# MainBoard_v1_1.net
KiCad netlist of a schematic drawn in EAGLE
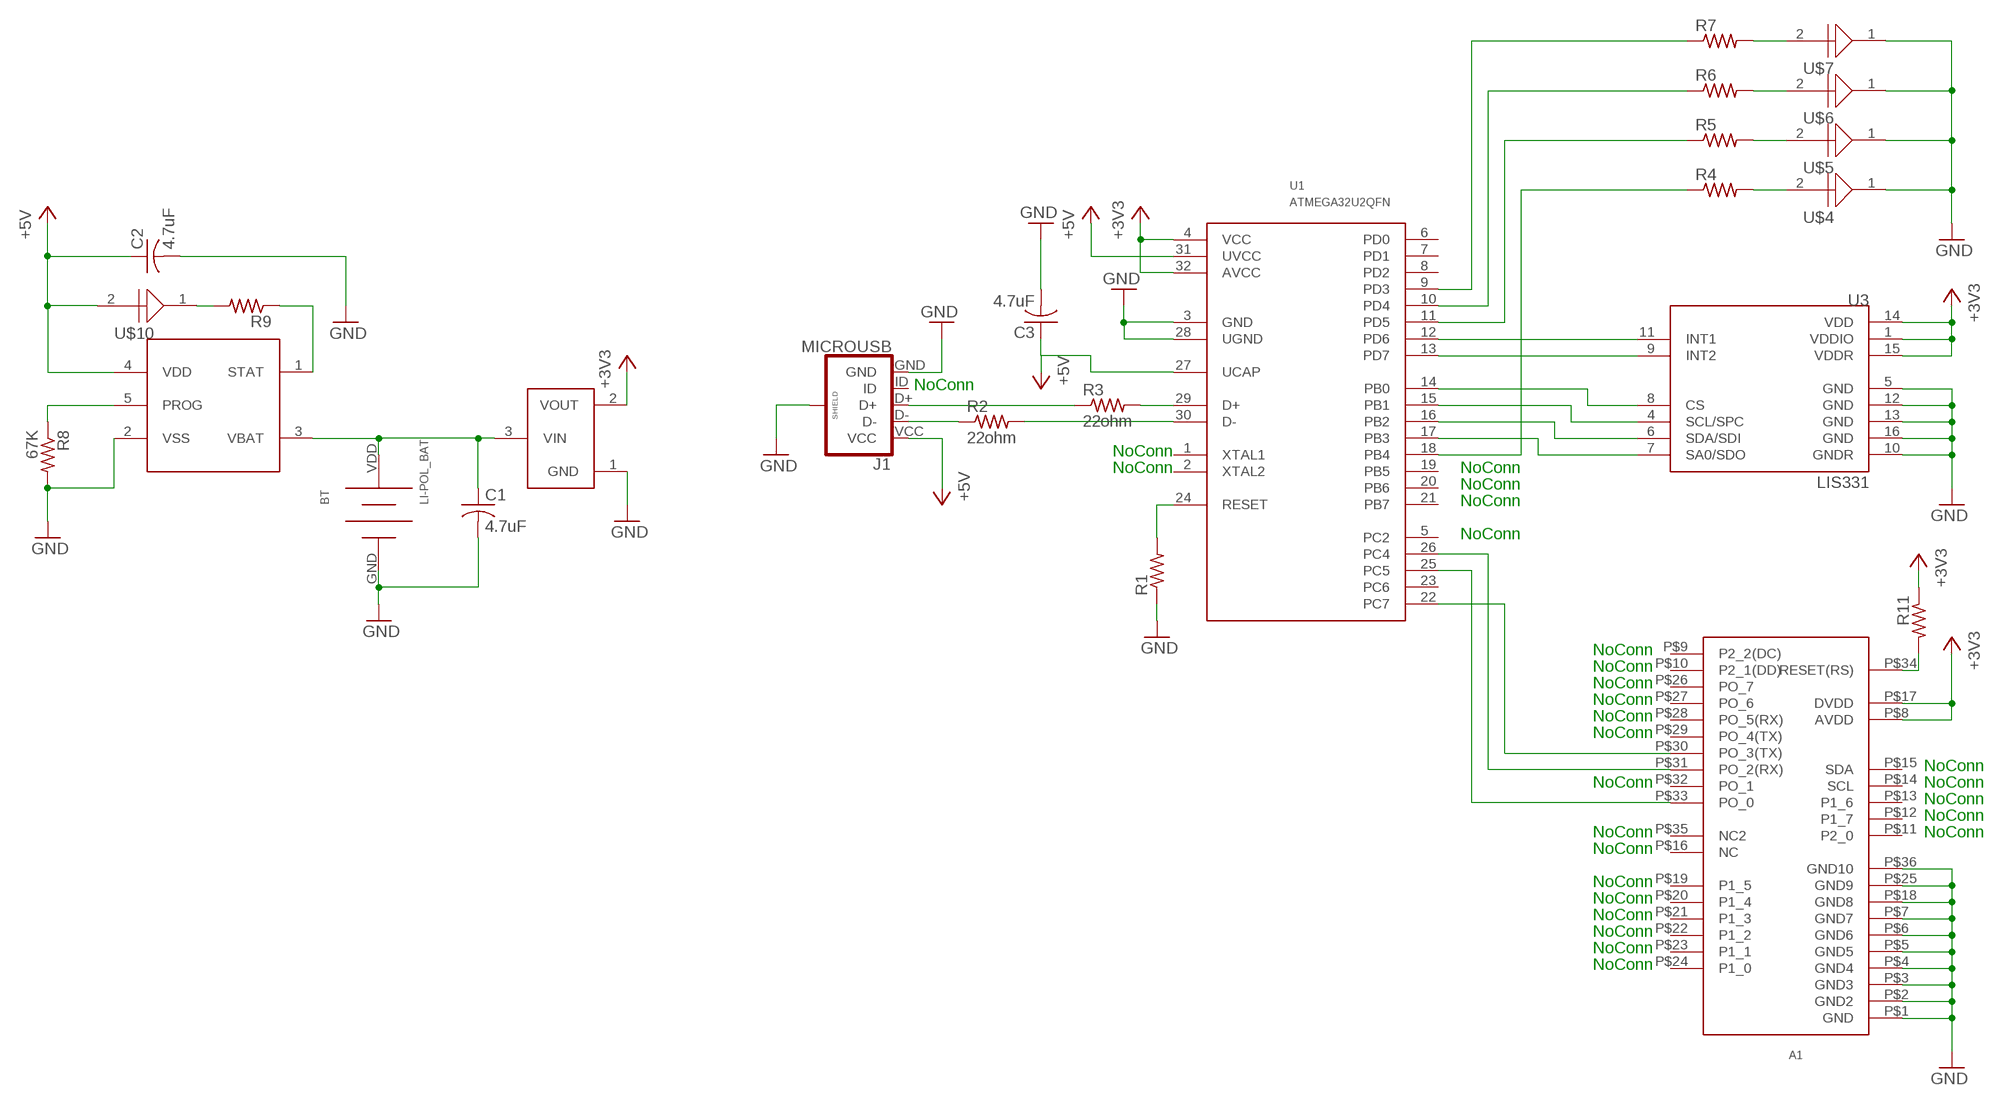
[diagram p0: schematic, sheet 1]

(export (version "E")
  (design (tool "Eeschema 10.0.6"))
  (components
    (comp (ref "A1")
      (value "BLE113-A")
      (footprint "eagle-import:BLUETOOTHNS")
      (libsource (lib "eagle-import") (part "BLE113-A"))
    )
    (comp (ref "BT")
      (value "LI-POL_BAT")
      (footprint "eagle-import:LI-POLY_28")
      (libsource (lib "eagle-import") (part "LI-POL_BAT"))
    )
    (comp (ref "C1")
      (value "4.7uF")
      (footprint "eagle-import:C0402")
      (libsource (lib "eagle-import") (part "C-USC0402"))
    )
    (comp (ref "C2")
      (value "4.7uF")
      (footprint "eagle-import:C0402")
      (libsource (lib "eagle-import") (part "C-USC0402"))
    )
    (comp (ref "C3")
      (value "4.7uF")
      (footprint "eagle-import:C0402")
      (libsource (lib "eagle-import") (part "C-USC0402"))
    )
    (comp (ref "J1")
      (value "MICROUSB")
      (footprint "eagle-import:MICROUSB")
      (libsource (lib "eagle-import") (part "MICROUSB"))
    )
    (comp (ref "R1")
      (value "R-US_R0402")
      (footprint "eagle-import:R0402")
      (libsource (lib "eagle-import") (part "R-US_R0402"))
    )
    (comp (ref "R2")
      (value "22ohm")
      (footprint "eagle-import:R0402")
      (libsource (lib "eagle-import") (part "R-US_R0402"))
    )
    (comp (ref "R3")
      (value "22ohm")
      (footprint "eagle-import:R0402")
      (libsource (lib "eagle-import") (part "R-US_R0402"))
    )
    (comp (ref "R4")
      (value "R-US_R0402")
      (footprint "eagle-import:R0402")
      (libsource (lib "eagle-import") (part "R-US_R0402"))
    )
    (comp (ref "R5")
      (value "R-US_R0402")
      (footprint "eagle-import:R0402")
      (libsource (lib "eagle-import") (part "R-US_R0402"))
    )
    (comp (ref "R6")
      (value "R-US_R0402")
      (footprint "eagle-import:R0402")
      (libsource (lib "eagle-import") (part "R-US_R0402"))
    )
    (comp (ref "R7")
      (value "R-US_R0402")
      (footprint "eagle-import:R0402")
      (libsource (lib "eagle-import") (part "R-US_R0402"))
    )
    (comp (ref "R8")
      (value "67K")
      (footprint "eagle-import:R0402")
      (libsource (lib "eagle-import") (part "R-US_R0402"))
    )
    (comp (ref "R9")
      (value "R-US_R0402")
      (footprint "eagle-import:R0402")
      (libsource (lib "eagle-import") (part "R-US_R0402"))
    )
    (comp (ref "R11")
      (value "R-US_R0402")
      (footprint "eagle-import:R0402")
      (libsource (lib "eagle-import") (part "R-US_R0402"))
    )
    (comp (ref "U$4")
      (value "LED_0402")
      (footprint "eagle-import:R0402")
      (libsource (lib "eagle-import") (part "LED_0402"))
    )
    (comp (ref "U$5")
      (value "LED_0402")
      (footprint "eagle-import:R0402")
      (libsource (lib "eagle-import") (part "LED_0402"))
    )
    (comp (ref "U$6")
      (value "LED_0402")
      (footprint "eagle-import:R0402")
      (libsource (lib "eagle-import") (part "LED_0402"))
    )
    (comp (ref "U$7")
      (value "LED_0402")
      (footprint "eagle-import:R0402")
      (libsource (lib "eagle-import") (part "LED_0402"))
    )
    (comp (ref "U$10")
      (value "LED_0402")
      (footprint "eagle-import:R0402")
      (libsource (lib "eagle-import") (part "LED_0402"))
    )
    (comp (ref "U1")
      (value "ATMEGA32U2QFN")
      (footprint "eagle-import:QFN-32")
      (libsource (lib "eagle-import") (part "ATMEGA32U2QFN"))
    )
    (comp (ref "U2")
      (value "MCP738312")
      (footprint "eagle-import:SOT23-5")
      (libsource (lib "eagle-import") (part "MCP738312"))
    )
    (comp (ref "U3")
      (value "LIS331")
      (footprint "eagle-import:LGA16-3MM")
      (libsource (lib "eagle-import") (part "LIS331"))
    )
    (comp (ref "U5")
      (value "REGULATOR")
      (footprint "eagle-import:SOT23-3")
      (libsource (lib "eagle-import") (part "REGULATOR"))
    )
  )
  (nets
    (net (code "1") (name "+3V3") (class "Default")
      (node (ref "A1") (pin "P$17") (pinfunction "DVDD_P$17") (pintype "bidirectional"))
      (node (ref "A1") (pin "P$8") (pinfunction "AVDD_P$8") (pintype "bidirectional"))
      (node (ref "R11") (pin "1") (pinfunction "1_1") (pintype "passive"))
      (node (ref "U1") (pin "32") (pinfunction "AVCC_32") (pintype "bidirectional"))
      (node (ref "U1") (pin "4") (pinfunction "VCC_4") (pintype "bidirectional"))
      (node (ref "U3") (pin "1") (pinfunction "VDDIO_1") (pintype "bidirectional"))
      (node (ref "U3") (pin "14") (pinfunction "VDD_14") (pintype "bidirectional"))
      (node (ref "U3") (pin "15") (pinfunction "VDDR_15") (pintype "bidirectional"))
      (node (ref "U5") (pin "2") (pinfunction "VOUT_2") (pintype "bidirectional"))
    )
    (net (code "2") (name "+5V") (class "Default")
      (node (ref "C2") (pin "1") (pinfunction "1_1") (pintype "passive"))
      (node (ref "C3") (pin "1") (pinfunction "1_1") (pintype "passive"))
      (node (ref "J1") (pin "VCC") (pinfunction "VCC_VCC") (pintype "bidirectional"))
      (node (ref "U$10") (pin "2") (pinfunction "P2_2") (pintype "bidirectional"))
      (node (ref "U1") (pin "27") (pinfunction "UCAP_27") (pintype "bidirectional"))
      (node (ref "U1") (pin "31") (pinfunction "UVCC_31") (pintype "bidirectional"))
      (node (ref "U2") (pin "4") (pinfunction "VDD_4") (pintype "bidirectional"))
    )
    (net (code "3") (name "GND") (class "Default")
      (node (ref "A1") (pin "P$1") (pinfunction "GND_P$1") (pintype "bidirectional"))
      (node (ref "A1") (pin "P$18") (pinfunction "GND8_P$18") (pintype "bidirectional"))
      (node (ref "A1") (pin "P$2") (pinfunction "GND2_P$2") (pintype "bidirectional"))
      (node (ref "A1") (pin "P$25") (pinfunction "GND9_P$25") (pintype "bidirectional"))
      (node (ref "A1") (pin "P$3") (pinfunction "GND3_P$3") (pintype "bidirectional"))
      (node (ref "A1") (pin "P$36") (pinfunction "GND10_P$36") (pintype "bidirectional"))
      (node (ref "A1") (pin "P$4") (pinfunction "GND4_P$4") (pintype "bidirectional"))
      (node (ref "A1") (pin "P$5") (pinfunction "GND5_P$5") (pintype "bidirectional"))
      (node (ref "A1") (pin "P$6") (pinfunction "GND6_P$6") (pintype "bidirectional"))
      (node (ref "A1") (pin "P$7") (pinfunction "GND7_P$7") (pintype "bidirectional"))
      (node (ref "BT") (pin "GND") (pinfunction "GND_GND") (pintype "bidirectional"))
      (node (ref "C1") (pin "2") (pinfunction "2_2") (pintype "passive"))
      (node (ref "C2") (pin "2") (pinfunction "2_2") (pintype "passive"))
      (node (ref "C3") (pin "2") (pinfunction "2_2") (pintype "passive"))
      (node (ref "J1") (pin "GD1") (pinfunction "SHIELD_GD1") (pintype "bidirectional"))
      (node (ref "J1") (pin "GD2") (pinfunction "SHIELD_GD2") (pintype "bidirectional"))
      (node (ref "J1") (pin "GD3") (pinfunction "SHIELD_GD3") (pintype "bidirectional"))
      (node (ref "J1") (pin "GD4") (pinfunction "SHIELD_GD4") (pintype "bidirectional"))
      (node (ref "J1") (pin "GND") (pinfunction "GND_GND") (pintype "bidirectional"))
      (node (ref "R1") (pin "1") (pinfunction "1_1") (pintype "passive"))
      (node (ref "R8") (pin "2") (pinfunction "2_2") (pintype "passive"))
      (node (ref "U$4") (pin "1") (pinfunction "P1_1") (pintype "bidirectional"))
      (node (ref "U$5") (pin "1") (pinfunction "P1_1") (pintype "bidirectional"))
      (node (ref "U$6") (pin "1") (pinfunction "P1_1") (pintype "bidirectional"))
      (node (ref "U$7") (pin "1") (pinfunction "P1_1") (pintype "bidirectional"))
      (node (ref "U1") (pin "28") (pinfunction "UGND_28") (pintype "bidirectional"))
      (node (ref "U1") (pin "3") (pinfunction "GND_3") (pintype "bidirectional"))
      (node (ref "U2") (pin "2") (pinfunction "VSS_2") (pintype "bidirectional"))
      (node (ref "U3") (pin "10") (pinfunction "GNDR_10") (pintype "bidirectional"))
      (node (ref "U3") (pin "12") (pinfunction "GND_12") (pintype "bidirectional"))
      (node (ref "U3") (pin "13") (pinfunction "GND_13") (pintype "bidirectional"))
      (node (ref "U3") (pin "16") (pinfunction "GND_16") (pintype "bidirectional"))
      (node (ref "U3") (pin "5") (pinfunction "GND_5") (pintype "bidirectional"))
      (node (ref "U5") (pin "1") (pinfunction "GND_1") (pintype "bidirectional"))
    )
    (net (code "4") (name "Net-(A1-PO_0)") (class "Default")
      (node (ref "A1") (pin "P$33") (pinfunction "PO_0_P$33") (pintype "bidirectional"))
      (node (ref "U1") (pin "25") (pinfunction "PC5_25") (pintype "bidirectional"))
    )
    (net (code "5") (name "Net-(A1-PO_2(RX))") (class "Default")
      (node (ref "A1") (pin "P$31") (pinfunction "PO_2(RX)_P$31") (pintype "bidirectional"))
      (node (ref "U1") (pin "26") (pinfunction "PC4_26") (pintype "bidirectional"))
    )
    (net (code "6") (name "Net-(A1-PO_3(TX))") (class "Default")
      (node (ref "A1") (pin "P$30") (pinfunction "PO_3(TX)_P$30") (pintype "bidirectional"))
      (node (ref "U1") (pin "22") (pinfunction "PC7_22") (pintype "bidirectional"))
    )
    (net (code "7") (name "Net-(A1-RESET(RS))") (class "Default")
      (node (ref "A1") (pin "P$34") (pinfunction "RESET(RS)_P$34") (pintype "bidirectional"))
      (node (ref "R11") (pin "2") (pinfunction "2_2") (pintype "passive"))
    )
    (net (code "8") (name "Net-(J1-PadD+)") (class "Default")
      (node (ref "J1") (pin "D+") (pinfunction "D+_D+") (pintype "bidirectional"))
      (node (ref "R3") (pin "1") (pinfunction "1_1") (pintype "passive"))
    )
    (net (code "9") (name "Net-(J1-PadD-)") (class "Default")
      (node (ref "J1") (pin "D-") (pinfunction "D-_D-") (pintype "bidirectional"))
      (node (ref "R2") (pin "1") (pinfunction "1_1") (pintype "passive"))
    )
    (net (code "10") (name "Net-(U$4-P2)") (class "Default")
      (node (ref "R4") (pin "2") (pinfunction "2_2") (pintype "passive"))
      (node (ref "U$4") (pin "2") (pinfunction "P2_2") (pintype "bidirectional"))
    )
    (net (code "11") (name "Net-(U$5-P2)") (class "Default")
      (node (ref "R5") (pin "2") (pinfunction "2_2") (pintype "passive"))
      (node (ref "U$5") (pin "2") (pinfunction "P2_2") (pintype "bidirectional"))
    )
    (net (code "12") (name "Net-(U$6-P2)") (class "Default")
      (node (ref "R6") (pin "2") (pinfunction "2_2") (pintype "passive"))
      (node (ref "U$6") (pin "2") (pinfunction "P2_2") (pintype "bidirectional"))
    )
    (net (code "13") (name "Net-(U$7-P2)") (class "Default")
      (node (ref "R7") (pin "2") (pinfunction "2_2") (pintype "passive"))
      (node (ref "U$7") (pin "2") (pinfunction "P2_2") (pintype "bidirectional"))
    )
    (net (code "14") (name "Net-(U$10-P1)") (class "Default")
      (node (ref "R9") (pin "2") (pinfunction "2_2") (pintype "passive"))
      (node (ref "U$10") (pin "1") (pinfunction "P1_1") (pintype "bidirectional"))
    )
    (net (code "15") (name "Net-(U1-D+)") (class "Default")
      (node (ref "R3") (pin "2") (pinfunction "2_2") (pintype "passive"))
      (node (ref "U1") (pin "29") (pinfunction "D+_29") (pintype "bidirectional"))
    )
    (net (code "16") (name "Net-(U1-D-)") (class "Default")
      (node (ref "R2") (pin "2") (pinfunction "2_2") (pintype "passive"))
      (node (ref "U1") (pin "30") (pinfunction "D-_30") (pintype "bidirectional"))
    )
    (net (code "17") (name "Net-(U1-PB0)") (class "Default")
      (node (ref "U1") (pin "14") (pinfunction "PB0_14") (pintype "bidirectional"))
      (node (ref "U3") (pin "8") (pinfunction "CS_8") (pintype "bidirectional"))
    )
    (net (code "18") (name "Net-(U1-PB1)") (class "Default")
      (node (ref "U1") (pin "15") (pinfunction "PB1_15") (pintype "bidirectional"))
      (node (ref "U3") (pin "4") (pinfunction "SCL/SPC_4") (pintype "bidirectional"))
    )
    (net (code "19") (name "Net-(U1-PB2)") (class "Default")
      (node (ref "U1") (pin "16") (pinfunction "PB2_16") (pintype "bidirectional"))
      (node (ref "U3") (pin "6") (pinfunction "SDA/SDI_6") (pintype "bidirectional"))
    )
    (net (code "20") (name "Net-(U1-PB3)") (class "Default")
      (node (ref "U1") (pin "17") (pinfunction "PB3_17") (pintype "bidirectional"))
      (node (ref "U3") (pin "7") (pinfunction "SA0/SDO_7") (pintype "bidirectional"))
    )
    (net (code "21") (name "Net-(U1-PB4)") (class "Default")
      (node (ref "R4") (pin "1") (pinfunction "1_1") (pintype "passive"))
      (node (ref "U1") (pin "18") (pinfunction "PB4_18") (pintype "bidirectional"))
    )
    (net (code "22") (name "Net-(U1-PD3)") (class "Default")
      (node (ref "R7") (pin "1") (pinfunction "1_1") (pintype "passive"))
      (node (ref "U1") (pin "9") (pinfunction "PD3_9") (pintype "bidirectional"))
    )
    (net (code "23") (name "Net-(U1-PD4)") (class "Default")
      (node (ref "R6") (pin "1") (pinfunction "1_1") (pintype "passive"))
      (node (ref "U1") (pin "10") (pinfunction "PD4_10") (pintype "bidirectional"))
    )
    (net (code "24") (name "Net-(U1-PD5)") (class "Default")
      (node (ref "R5") (pin "1") (pinfunction "1_1") (pintype "passive"))
      (node (ref "U1") (pin "11") (pinfunction "PD5_11") (pintype "bidirectional"))
    )
    (net (code "25") (name "Net-(U1-PD6)") (class "Default")
      (node (ref "U1") (pin "12") (pinfunction "PD6_12") (pintype "bidirectional"))
      (node (ref "U3") (pin "11") (pinfunction "INT1_11") (pintype "bidirectional"))
    )
    (net (code "26") (name "Net-(U1-PD7)") (class "Default")
      (node (ref "U1") (pin "13") (pinfunction "PD7_13") (pintype "bidirectional"))
      (node (ref "U3") (pin "9") (pinfunction "INT2_9") (pintype "bidirectional"))
    )
    (net (code "27") (name "Net-(U1-RESET)") (class "Default")
      (node (ref "R1") (pin "2") (pinfunction "2_2") (pintype "passive"))
      (node (ref "U1") (pin "24") (pinfunction "RESET_24") (pintype "bidirectional"))
    )
    (net (code "28") (name "Net-(U2-PROG)") (class "Default")
      (node (ref "R8") (pin "1") (pinfunction "1_1") (pintype "passive"))
      (node (ref "U2") (pin "5") (pinfunction "PROG_5") (pintype "bidirectional"))
    )
    (net (code "29") (name "Net-(U2-STAT)") (class "Default")
      (node (ref "R9") (pin "1") (pinfunction "1_1") (pintype "passive"))
      (node (ref "U2") (pin "1") (pinfunction "STAT_1") (pintype "bidirectional"))
    )
    (net (code "30") (name "Net-(U2-VBAT)") (class "Default")
      (node (ref "BT") (pin "VDD") (pinfunction "VDD_VDD") (pintype "bidirectional"))
      (node (ref "C1") (pin "1") (pinfunction "1_1") (pintype "passive"))
      (node (ref "U2") (pin "3") (pinfunction "VBAT_3") (pintype "bidirectional"))
      (node (ref "U5") (pin "3") (pinfunction "VIN_3") (pintype "bidirectional"))
    )
    (net (code "31") (name "unconnected-(A1-NC-PadP$16)") (class "Default")
      (node (ref "A1") (pin "P$16") (pinfunction "NC_P$16") (pintype "bidirectional"))
    )
    (net (code "32") (name "unconnected-(A1-NC2-PadP$35)") (class "Default")
      (node (ref "A1") (pin "P$35") (pinfunction "NC2_P$35") (pintype "bidirectional"))
    )
    (net (code "33") (name "unconnected-(A1-P1_0-PadP$24)") (class "Default")
      (node (ref "A1") (pin "P$24") (pinfunction "P1_0_P$24") (pintype "bidirectional"))
    )
    (net (code "34") (name "unconnected-(A1-P1_1-PadP$23)") (class "Default")
      (node (ref "A1") (pin "P$23") (pinfunction "P1_1_P$23") (pintype "bidirectional"))
    )
    (net (code "35") (name "unconnected-(A1-P1_2-PadP$22)") (class "Default")
      (node (ref "A1") (pin "P$22") (pinfunction "P1_2_P$22") (pintype "bidirectional"))
    )
    (net (code "36") (name "unconnected-(A1-P1_3-PadP$21)") (class "Default")
      (node (ref "A1") (pin "P$21") (pinfunction "P1_3_P$21") (pintype "bidirectional"))
    )
    (net (code "37") (name "unconnected-(A1-P1_4-PadP$20)") (class "Default")
      (node (ref "A1") (pin "P$20") (pinfunction "P1_4_P$20") (pintype "bidirectional"))
    )
    (net (code "38") (name "unconnected-(A1-P1_5-PadP$19)") (class "Default")
      (node (ref "A1") (pin "P$19") (pinfunction "P1_5_P$19") (pintype "bidirectional"))
    )
    (net (code "39") (name "unconnected-(A1-P1_6-PadP$13)") (class "Default")
      (node (ref "A1") (pin "P$13") (pinfunction "P1_6_P$13") (pintype "bidirectional"))
    )
    (net (code "40") (name "unconnected-(A1-P1_7-PadP$12)") (class "Default")
      (node (ref "A1") (pin "P$12") (pinfunction "P1_7_P$12") (pintype "bidirectional"))
    )
    (net (code "41") (name "unconnected-(A1-P2_0-PadP$11)") (class "Default")
      (node (ref "A1") (pin "P$11") (pinfunction "P2_0_P$11") (pintype "bidirectional"))
    )
    (net (code "42") (name "unconnected-(A1-P2_1(DD)-PadP$10)") (class "Default")
      (node (ref "A1") (pin "P$10") (pinfunction "P2_1(DD)_P$10") (pintype "bidirectional"))
    )
    (net (code "43") (name "unconnected-(A1-P2_2(DC)-PadP$9)") (class "Default")
      (node (ref "A1") (pin "P$9") (pinfunction "P2_2(DC)_P$9") (pintype "bidirectional"))
    )
    (net (code "44") (name "unconnected-(A1-PO_1-PadP$32)") (class "Default")
      (node (ref "A1") (pin "P$32") (pinfunction "PO_1_P$32") (pintype "bidirectional"))
    )
    (net (code "45") (name "unconnected-(A1-PO_4(TX)-PadP$29)") (class "Default")
      (node (ref "A1") (pin "P$29") (pinfunction "PO_4(TX)_P$29") (pintype "bidirectional"))
    )
    (net (code "46") (name "unconnected-(A1-PO_5(RX)-PadP$28)") (class "Default")
      (node (ref "A1") (pin "P$28") (pinfunction "PO_5(RX)_P$28") (pintype "bidirectional"))
    )
    (net (code "47") (name "unconnected-(A1-PO_6-PadP$27)") (class "Default")
      (node (ref "A1") (pin "P$27") (pinfunction "PO_6_P$27") (pintype "bidirectional"))
    )
    (net (code "48") (name "unconnected-(A1-PO_7-PadP$26)") (class "Default")
      (node (ref "A1") (pin "P$26") (pinfunction "PO_7_P$26") (pintype "bidirectional"))
    )
    (net (code "49") (name "unconnected-(A1-SCL-PadP$14)") (class "Default")
      (node (ref "A1") (pin "P$14") (pinfunction "SCL_P$14") (pintype "bidirectional"))
    )
    (net (code "50") (name "unconnected-(A1-SDA-PadP$15)") (class "Default")
      (node (ref "A1") (pin "P$15") (pinfunction "SDA_P$15") (pintype "bidirectional"))
    )
    (net (code "51") (name "unconnected-(J1-PadID)") (class "Default")
      (node (ref "J1") (pin "ID") (pinfunction "ID_ID") (pintype "bidirectional"))
    )
    (net (code "52") (name "unconnected-(U1-PB5-Pad19)") (class "Default")
      (node (ref "U1") (pin "19") (pinfunction "PB5_19") (pintype "bidirectional"))
    )
    (net (code "53") (name "unconnected-(U1-PB6-Pad20)") (class "Default")
      (node (ref "U1") (pin "20") (pinfunction "PB6_20") (pintype "bidirectional"))
    )
    (net (code "54") (name "unconnected-(U1-PB7-Pad21)") (class "Default")
      (node (ref "U1") (pin "21") (pinfunction "PB7_21") (pintype "bidirectional"))
    )
    (net (code "55") (name "unconnected-(U1-PC2-Pad5)") (class "Default")
      (node (ref "U1") (pin "5") (pinfunction "PC2_5") (pintype "bidirectional"))
    )
    (net (code "56") (name "unconnected-(U1-PC6-Pad23)") (class "Default")
      (node (ref "U1") (pin "23") (pinfunction "PC6_23") (pintype "bidirectional"))
    )
    (net (code "57") (name "unconnected-(U1-PD0-Pad6)") (class "Default")
      (node (ref "U1") (pin "6") (pinfunction "PD0_6") (pintype "bidirectional"))
    )
    (net (code "58") (name "unconnected-(U1-PD1-Pad7)") (class "Default")
      (node (ref "U1") (pin "7") (pinfunction "PD1_7") (pintype "bidirectional"))
    )
    (net (code "59") (name "unconnected-(U1-PD2-Pad8)") (class "Default")
      (node (ref "U1") (pin "8") (pinfunction "PD2_8") (pintype "bidirectional"))
    )
    (net (code "60") (name "unconnected-(U1-XTAL1-Pad1)") (class "Default")
      (node (ref "U1") (pin "1") (pinfunction "XTAL1_1") (pintype "bidirectional"))
    )
    (net (code "61") (name "unconnected-(U1-XTAL2-Pad2)") (class "Default")
      (node (ref "U1") (pin "2") (pinfunction "XTAL2_2") (pintype "bidirectional"))
    )
  )
)
